# W076-3-20.net
KiCad netlist of a schematic drawn in EAGLE
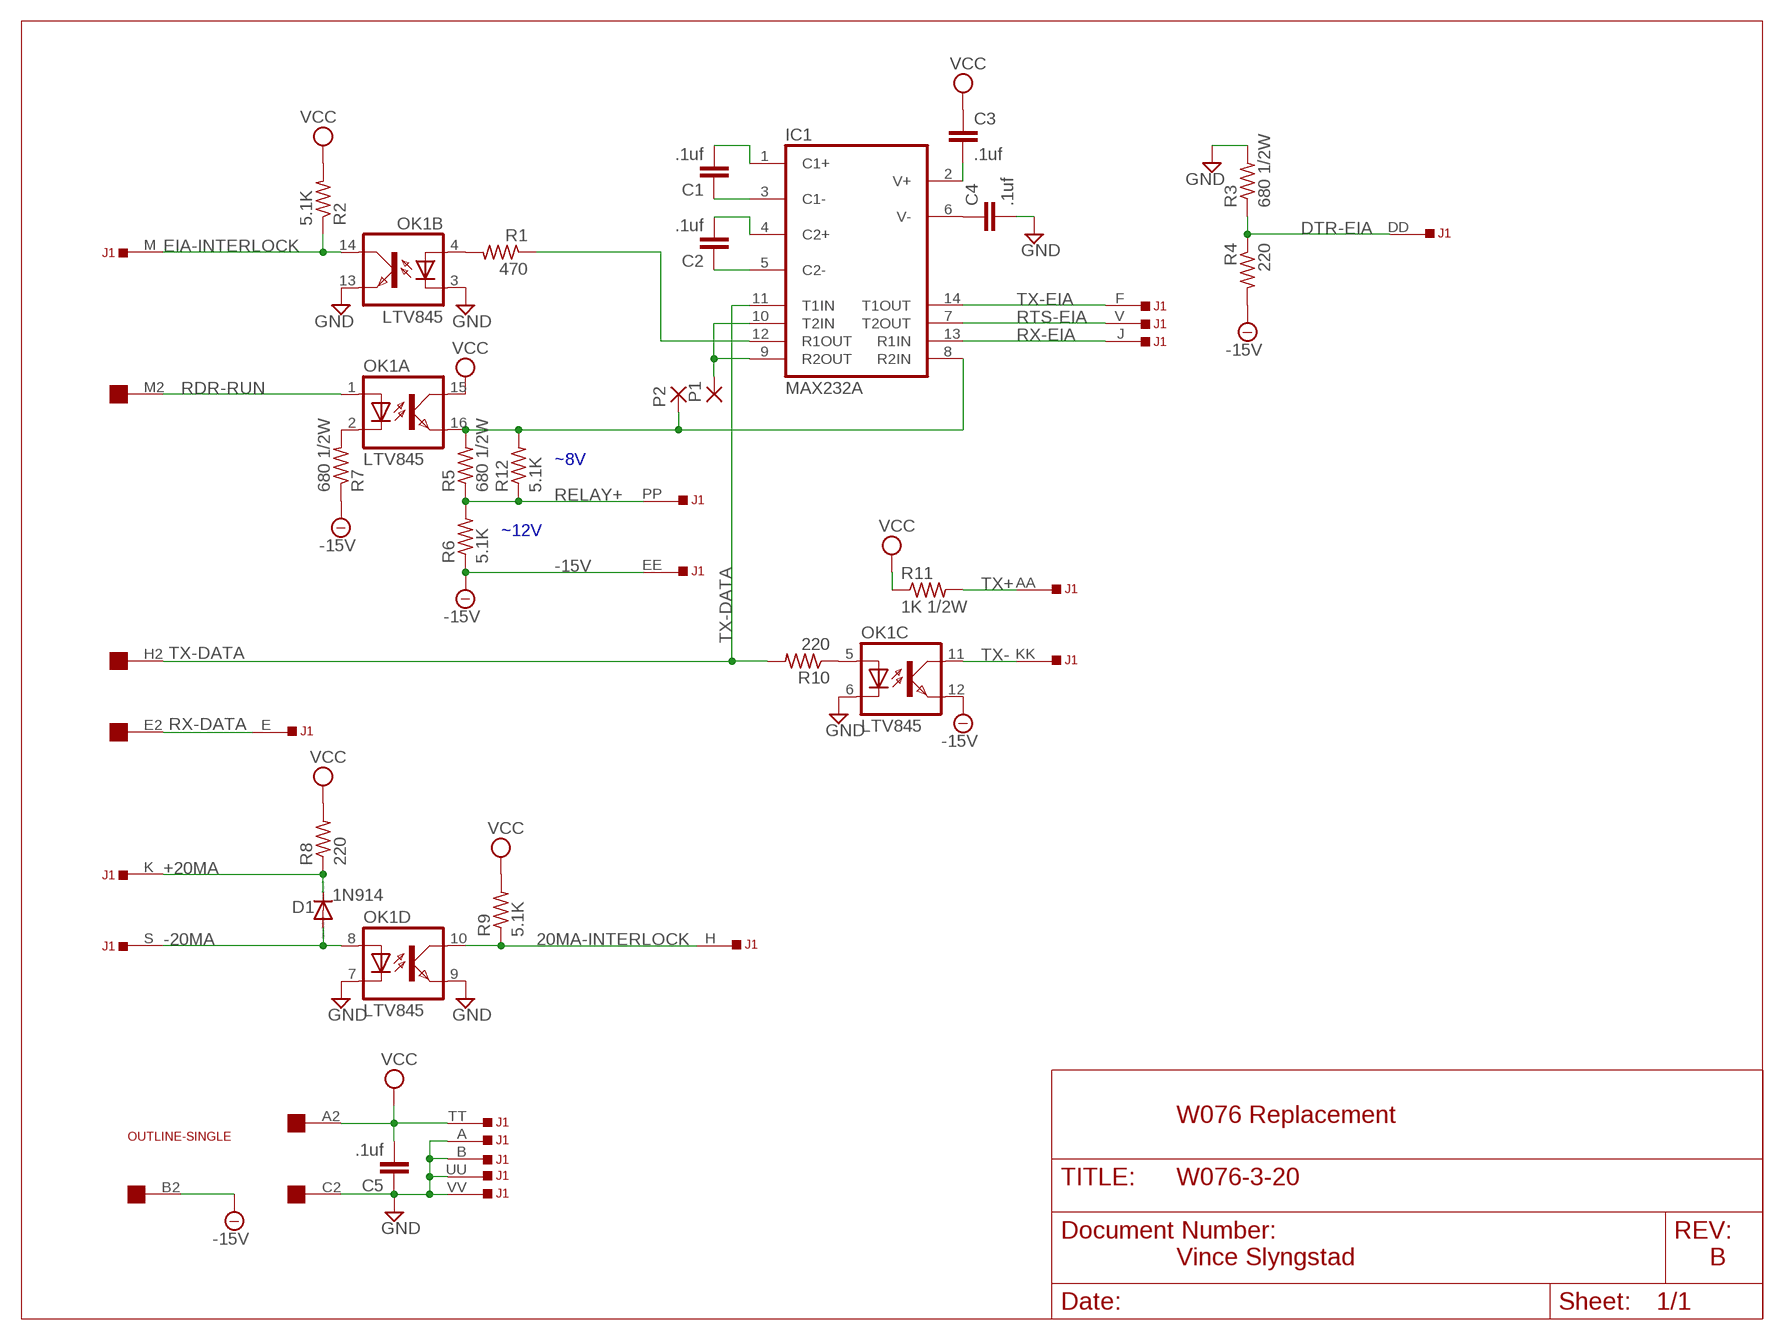
[diagram p0: schematic, sheet 1]

(export (version "E")
  (design (tool "Eeschema 10.0.6"))
  (components
    (comp (ref "C1")
      (value ".1uf")
      (footprint "eagle-import:C050-025X075")
      (libsource (lib "eagle-import") (part "C-EU050-025X075"))
    )
    (comp (ref "C2")
      (value ".1uf")
      (footprint "eagle-import:C050-025X075")
      (libsource (lib "eagle-import") (part "C-EU050-025X075"))
    )
    (comp (ref "C3")
      (value ".1uf")
      (footprint "eagle-import:C050-025X075")
      (libsource (lib "eagle-import") (part "C-EU050-025X075"))
    )
    (comp (ref "C4")
      (value ".1uf")
      (footprint "eagle-import:C050-025X075")
      (libsource (lib "eagle-import") (part "C-EU050-025X075"))
    )
    (comp (ref "C5")
      (value ".1uf")
      (footprint "eagle-import:C050-025X075")
      (libsource (lib "eagle-import") (part "C-EU050-025X075"))
    )
    (comp (ref "D1")
      (value "1N914")
      (footprint "eagle-import:DO41-10")
      (libsource (lib "eagle-import") (part "1N4004"))
    )
    (comp (ref "IC1")
      (value "MAX232A")
      (footprint "eagle-import:DIL16")
      (fields (field (name "MF") "MAXIM") (field (name "MPN") "MAX232ACPE+"))
      (libsource (lib "eagle-import") (part "MAX232"))
    )
    (comp (ref "J1")
      (value "DEC40PINSH")
      (footprint "eagle-import:DEC40PINH")
      (libsource (lib "eagle-import") (part "DEC40PINSH"))
    )
    (comp (ref "OK1")
      (value "LTV845")
      (footprint "eagle-import:DIL16")
      (fields (field (name "MF") "VISHAY/TELEFUNKEN") (field (name "MPN") "ILQ1"))
      (libsource (lib "eagle-import") (part "ILQ1"))
    )
    (comp (ref "P1")
      (value "1,6/0,8")
      (footprint "eagle-import:1,6_0,8")
      (libsource (lib "eagle-import") (part "1,6/0,8"))
    )
    (comp (ref "P2")
      (value "1,6/0,8")
      (footprint "eagle-import:1,6_0,8")
      (libsource (lib "eagle-import") (part "1,6/0,8"))
    )
    (comp (ref "R1")
      (value "470")
      (footprint "eagle-import:0207_10")
      (libsource (lib "eagle-import") (part "R-US_0207/10"))
    )
    (comp (ref "R2")
      (value "5.1K")
      (footprint "eagle-import:0207_10")
      (libsource (lib "eagle-import") (part "R-US_0207/10"))
    )
    (comp (ref "R3")
      (value "680 1/2W")
      (footprint "eagle-import:0207_12")
      (libsource (lib "eagle-import") (part "R-US_0207/12"))
    )
    (comp (ref "R4")
      (value "220")
      (footprint "eagle-import:0207_10")
      (libsource (lib "eagle-import") (part "R-US_0207/10"))
    )
    (comp (ref "R5")
      (value "680 1/2W")
      (footprint "eagle-import:0207_12")
      (libsource (lib "eagle-import") (part "R-US_0207/12"))
    )
    (comp (ref "R6")
      (value "5.1K")
      (footprint "eagle-import:0207_10")
      (libsource (lib "eagle-import") (part "R-US_0207/10"))
    )
    (comp (ref "R7")
      (value "680 1/2W")
      (footprint "eagle-import:0207_12")
      (libsource (lib "eagle-import") (part "R-US_0207/12"))
    )
    (comp (ref "R8")
      (value "220")
      (footprint "eagle-import:0207_10")
      (libsource (lib "eagle-import") (part "R-US_0207/10"))
    )
    (comp (ref "R9")
      (value "5.1K")
      (footprint "eagle-import:0207_10")
      (libsource (lib "eagle-import") (part "R-US_0207/10"))
    )
    (comp (ref "R10")
      (value "220")
      (footprint "eagle-import:0207_10")
      (libsource (lib "eagle-import") (part "R-US_0207/10"))
    )
    (comp (ref "R11")
      (value "1K 1/2W")
      (footprint "eagle-import:0207_10")
      (libsource (lib "eagle-import") (part "R-US_0207/10"))
    )
    (comp (ref "R12")
      (value "5.1K")
      (footprint "eagle-import:0207_10")
      (libsource (lib "eagle-import") (part "R-US_0207/10"))
    )
    (comp (ref "U$2")
      (value "EDGE-1")
      (footprint "eagle-import:EDGE-CON1")
      (libsource (lib "eagle-import") (part "EDGE-1"))
    )
    (comp (ref "U$3")
      (value "OUTLINE-SINGLE")
      (footprint "eagle-import:SINGLE")
      (libsource (lib "eagle-import") (part "OUTLINE-SINGLE"))
    )
  )
  (nets
    (net (code "1") (name "-15V") (class "Default")
      (node (ref "J1") (pin "EE") (pinfunction "P_EE") (pintype "passive"))
      (node (ref "OK1") (pin "12") (pinfunction "EMIT_12") (pintype "passive"))
      (node (ref "R4") (pin "2") (pinfunction "2_2") (pintype "passive"))
      (node (ref "R6") (pin "1") (pinfunction "1_1") (pintype "passive"))
      (node (ref "R7") (pin "1") (pinfunction "1_1") (pintype "passive"))
      (node (ref "U$2") (pin "B2") (pinfunction "1_B2") (pintype "bidirectional"))
    )
    (net (code "2") (name "/+20MA") (class "Default")
      (node (ref "D1") (pin "C") (pinfunction "C_C") (pintype "passive"))
      (node (ref "J1") (pin "K") (pinfunction "P_K") (pintype "passive"))
      (node (ref "R8") (pin "1") (pinfunction "1_1") (pintype "passive"))
    )
    (net (code "3") (name "/-20MA") (class "Default")
      (node (ref "D1") (pin "A") (pinfunction "A_A") (pintype "passive"))
      (node (ref "J1") (pin "S") (pinfunction "P_S") (pintype "passive"))
      (node (ref "OK1") (pin "8") (pinfunction "A_8") (pintype "passive"))
    )
    (net (code "4") (name "/20MA-INTERLOCK") (class "Default")
      (node (ref "J1") (pin "H") (pinfunction "P_H") (pintype "passive"))
      (node (ref "OK1") (pin "10") (pinfunction "COL_10") (pintype "passive"))
      (node (ref "R9") (pin "1") (pinfunction "1_1") (pintype "passive"))
    )
    (net (code "5") (name "/DTR-EIA") (class "Default")
      (node (ref "J1") (pin "DD") (pinfunction "P_DD") (pintype "passive"))
      (node (ref "R3") (pin "1") (pinfunction "1_1") (pintype "passive"))
      (node (ref "R4") (pin "1") (pinfunction "1_1") (pintype "passive"))
    )
    (net (code "6") (name "/EIA-INTERLOCK") (class "Default")
      (node (ref "J1") (pin "M") (pinfunction "P_M") (pintype "passive"))
      (node (ref "OK1") (pin "14") (pinfunction "COL_14") (pintype "passive"))
      (node (ref "R2") (pin "1") (pinfunction "1_1") (pintype "passive"))
    )
    (net (code "7") (name "/RDR-RUN") (class "Default")
      (node (ref "OK1") (pin "1") (pinfunction "A_1") (pintype "passive"))
      (node (ref "U$2") (pin "M2") (pinfunction "1_M2") (pintype "bidirectional"))
    )
    (net (code "8") (name "/RELAY+") (class "Default")
      (node (ref "J1") (pin "PP") (pinfunction "P_PP") (pintype "passive"))
      (node (ref "R12") (pin "1") (pinfunction "1_1") (pintype "passive"))
      (node (ref "R5") (pin "1") (pinfunction "1_1") (pintype "passive"))
      (node (ref "R6") (pin "2") (pinfunction "2_2") (pintype "passive"))
    )
    (net (code "9") (name "/RTS-EIA") (class "Default")
      (node (ref "IC1") (pin "7") (pinfunction "T2OUT_7") (pintype "output"))
      (node (ref "J1") (pin "V") (pinfunction "P_V") (pintype "passive"))
    )
    (net (code "10") (name "/RX-DATA") (class "Default")
      (node (ref "J1") (pin "E") (pinfunction "P_E") (pintype "passive"))
      (node (ref "U$2") (pin "E2") (pinfunction "1_E2") (pintype "bidirectional"))
    )
    (net (code "11") (name "/RX-EIA") (class "Default")
      (node (ref "IC1") (pin "13") (pinfunction "R1IN_13") (pintype "input"))
      (node (ref "J1") (pin "J") (pinfunction "P_J") (pintype "passive"))
    )
    (net (code "12") (name "/TX+") (class "Default")
      (node (ref "J1") (pin "AA") (pinfunction "P_AA") (pintype "passive"))
      (node (ref "R11") (pin "2") (pinfunction "2_2") (pintype "passive"))
    )
    (net (code "13") (name "/TX-") (class "Default")
      (node (ref "J1") (pin "KK") (pinfunction "P_KK") (pintype "passive"))
      (node (ref "OK1") (pin "11") (pinfunction "COL_11") (pintype "passive"))
    )
    (net (code "14") (name "/TX-DATA") (class "Default")
      (node (ref "IC1") (pin "11") (pinfunction "T1IN_11") (pintype "input"))
      (node (ref "R10") (pin "2") (pinfunction "2_2") (pintype "passive"))
      (node (ref "U$2") (pin "H2") (pinfunction "1_H2") (pintype "bidirectional"))
    )
    (net (code "15") (name "/TX-EIA") (class "Default")
      (node (ref "IC1") (pin "14") (pinfunction "T1OUT_14") (pintype "output"))
      (node (ref "J1") (pin "F") (pinfunction "P_F") (pintype "passive"))
    )
    (net (code "16") (name "GND") (class "Default")
      (node (ref "C4") (pin "2") (pinfunction "2_2") (pintype "passive"))
      (node (ref "C5") (pin "1") (pinfunction "1_1") (pintype "passive"))
      (node (ref "J1") (pin "A") (pinfunction "P_A") (pintype "passive"))
      (node (ref "J1") (pin "B") (pinfunction "P_B") (pintype "passive"))
      (node (ref "J1") (pin "UU") (pinfunction "P_UU") (pintype "passive"))
      (node (ref "J1") (pin "VV") (pinfunction "P_VV") (pintype "passive"))
      (node (ref "OK1") (pin "13") (pinfunction "EMIT_13") (pintype "passive"))
      (node (ref "OK1") (pin "3") (pinfunction "C_3") (pintype "passive"))
      (node (ref "OK1") (pin "6") (pinfunction "C_6") (pintype "passive"))
      (node (ref "OK1") (pin "7") (pinfunction "C_7") (pintype "passive"))
      (node (ref "OK1") (pin "9") (pinfunction "EMIT_9") (pintype "passive"))
      (node (ref "R3") (pin "2") (pinfunction "2_2") (pintype "passive"))
      (node (ref "U$2") (pin "C2") (pinfunction "1_C2") (pintype "bidirectional"))
    )
    (net (code "17") (name "Net-(IC1A-C1+)") (class "Default")
      (node (ref "C1") (pin "2") (pinfunction "2_2") (pintype "passive"))
      (node (ref "IC1") (pin "1") (pinfunction "C1+_1") (pintype "bidirectional"))
    )
    (net (code "18") (name "Net-(IC1A-C1-)") (class "Default")
      (node (ref "C1") (pin "1") (pinfunction "1_1") (pintype "passive"))
      (node (ref "IC1") (pin "3") (pinfunction "C1-_3") (pintype "bidirectional"))
    )
    (net (code "19") (name "Net-(IC1A-C2+)") (class "Default")
      (node (ref "C2") (pin "2") (pinfunction "2_2") (pintype "passive"))
      (node (ref "IC1") (pin "4") (pinfunction "C2+_4") (pintype "bidirectional"))
    )
    (net (code "20") (name "Net-(IC1A-C2-)") (class "Default")
      (node (ref "C2") (pin "1") (pinfunction "1_1") (pintype "passive"))
      (node (ref "IC1") (pin "5") (pinfunction "C2-_5") (pintype "bidirectional"))
    )
    (net (code "21") (name "Net-(IC1A-R1OUT)") (class "Default")
      (node (ref "IC1") (pin "12") (pinfunction "R1OUT_12") (pintype "output"))
      (node (ref "R1") (pin "1") (pinfunction "1_1") (pintype "passive"))
    )
    (net (code "22") (name "Net-(IC1A-R2IN)") (class "Default")
      (node (ref "IC1") (pin "8") (pinfunction "R2IN_8") (pintype "input"))
      (node (ref "OK1") (pin "16") (pinfunction "EMIT_16") (pintype "passive"))
      (node (ref "P2") (pin "1") (pinfunction "P_1") (pintype "passive"))
      (node (ref "R12") (pin "2") (pinfunction "2_2") (pintype "passive"))
      (node (ref "R5") (pin "2") (pinfunction "2_2") (pintype "passive"))
    )
    (net (code "23") (name "Net-(IC1A-R2OUT)") (class "Default")
      (node (ref "IC1") (pin "10") (pinfunction "T2IN_10") (pintype "input"))
      (node (ref "IC1") (pin "9") (pinfunction "R2OUT_9") (pintype "output"))
      (node (ref "P1") (pin "1") (pinfunction "P_1") (pintype "passive"))
    )
    (net (code "24") (name "Net-(IC1A-V+)") (class "Default")
      (node (ref "C3") (pin "2") (pinfunction "2_2") (pintype "passive"))
      (node (ref "IC1") (pin "2") (pinfunction "V+_2") (pintype "bidirectional"))
    )
    (net (code "25") (name "Net-(IC1A-V-)") (class "Default")
      (node (ref "C4") (pin "1") (pinfunction "1_1") (pintype "passive"))
      (node (ref "IC1") (pin "6") (pinfunction "V-_6") (pintype "bidirectional"))
    )
    (net (code "26") (name "Net-(OK1A-C)") (class "Default")
      (node (ref "OK1") (pin "2") (pinfunction "C_2") (pintype "passive"))
      (node (ref "R7") (pin "2") (pinfunction "2_2") (pintype "passive"))
    )
    (net (code "27") (name "Net-(OK1B-A)") (class "Default")
      (node (ref "OK1") (pin "4") (pinfunction "A_4") (pintype "passive"))
      (node (ref "R1") (pin "2") (pinfunction "2_2") (pintype "passive"))
    )
    (net (code "28") (name "Net-(OK1C-A)") (class "Default")
      (node (ref "OK1") (pin "5") (pinfunction "A_5") (pintype "passive"))
      (node (ref "R10") (pin "1") (pinfunction "1_1") (pintype "passive"))
    )
    (net (code "29") (name "VCC") (class "Default")
      (node (ref "C3") (pin "1") (pinfunction "1_1") (pintype "passive"))
      (node (ref "C5") (pin "2") (pinfunction "2_2") (pintype "passive"))
      (node (ref "J1") (pin "TT") (pinfunction "P_TT") (pintype "passive"))
      (node (ref "OK1") (pin "15") (pinfunction "COL_15") (pintype "passive"))
      (node (ref "R11") (pin "1") (pinfunction "1_1") (pintype "passive"))
      (node (ref "R2") (pin "2") (pinfunction "2_2") (pintype "passive"))
      (node (ref "R8") (pin "2") (pinfunction "2_2") (pintype "passive"))
      (node (ref "R9") (pin "2") (pinfunction "2_2") (pintype "passive"))
      (node (ref "U$2") (pin "A2") (pinfunction "1_A2") (pintype "bidirectional"))
    )
  )
)
